# INTERFACE_rev2.net
KiCad netlist of a schematic drawn in Altium Designer
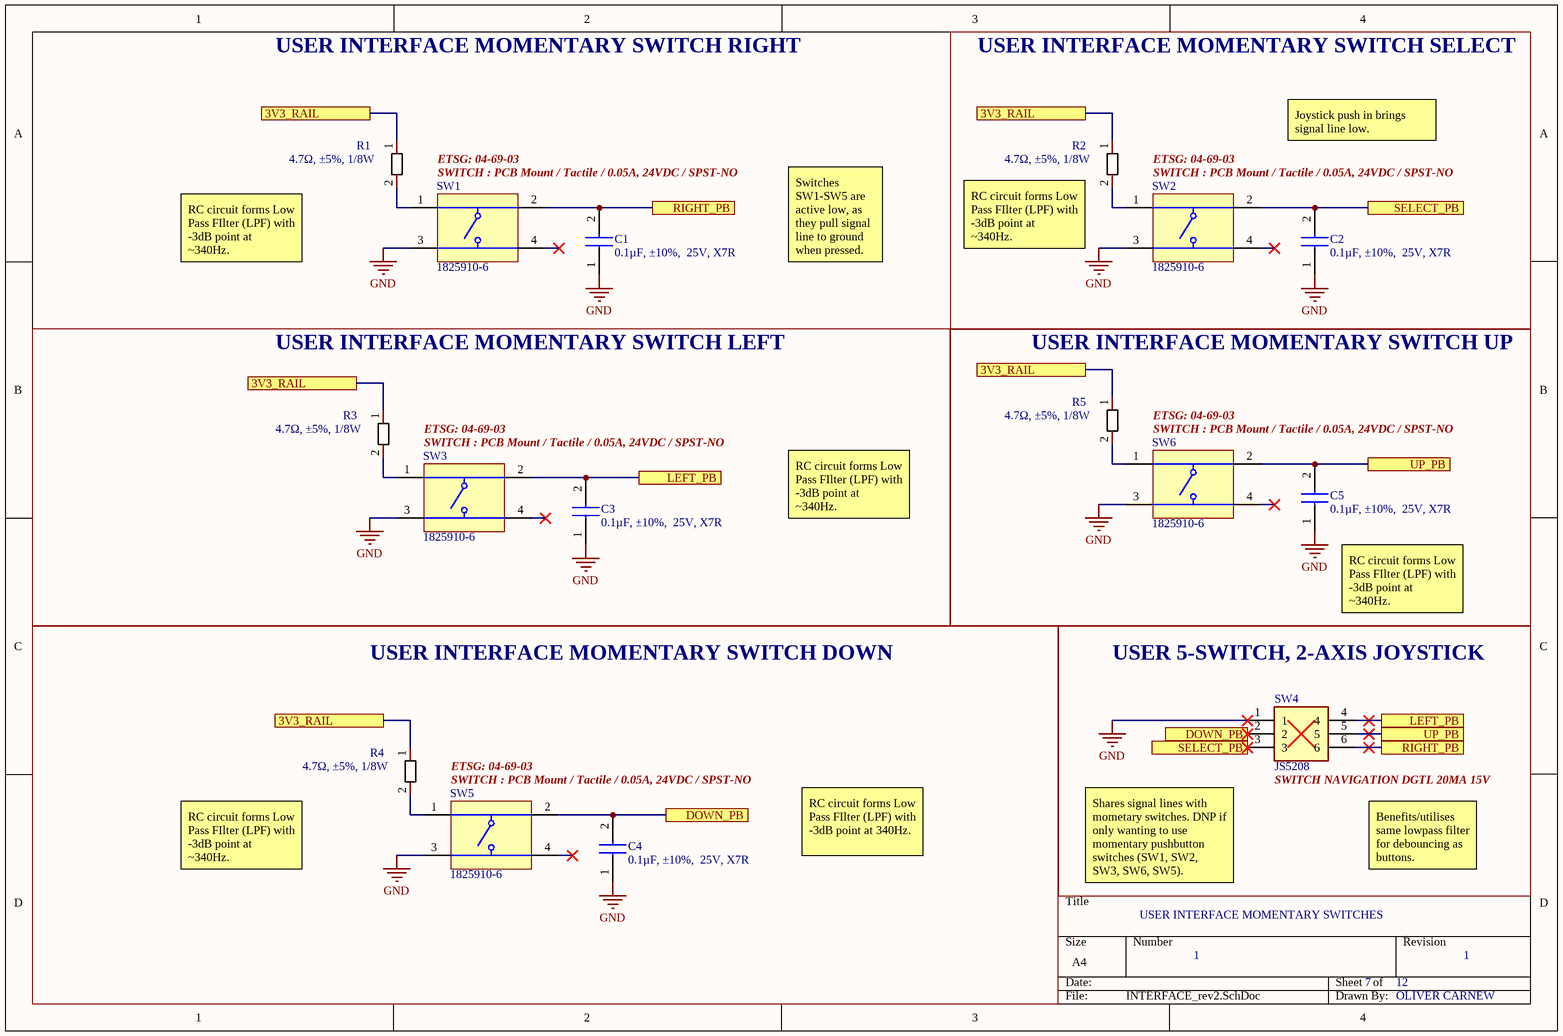
[diagram p0: INTERFACE_rev2.SchDoc]

(export (version "E")
  (design (tool "Eeschema 10.0.6"))
  (components
    (comp (ref "C1")
      (value "0.1µF, ±10%,  25V, X7R")
      (footprint "SamacSys:CAPC1005X55N")
      (description "Capacitor CAP CER 0.1UF 25V X7R 0402 CL05B104KA5NNNC")
      (fields
        (field (name "MANUFACTURER_PART_NUMBER") "CL05B104KA5NNNC")
        (field (name "MOUSER PART NUMBER") "187-CL05B104KA5NNNC")
      )
      (libsource (lib "*") (part "CL05B104KA5NNNC"))
    )
    (comp (ref "C2")
      (value "0.1µF, ±10%,  25V, X7R")
      (footprint "SamacSys:CAPC1005X55N")
      (description "Capacitor CAP CER 0.1UF 25V X7R 0402 CL05B104KA5NNNC")
      (fields
        (field (name "MANUFACTURER_PART_NUMBER") "CL05B104KA5NNNC")
        (field (name "MOUSER PART NUMBER") "187-CL05B104KA5NNNC")
      )
      (libsource (lib "*") (part "CL05B104KA5NNNC"))
    )
    (comp (ref "C3")
      (value "0.1µF, ±10%,  25V, X7R")
      (footprint "SamacSys:CAPC1005X55N")
      (description "Capacitor CAP CER 0.1UF 25V X7R 0402 CL05B104KA5NNNC")
      (fields
        (field (name "MANUFACTURER_PART_NUMBER") "CL05B104KA5NNNC")
        (field (name "MOUSER PART NUMBER") "187-CL05B104KA5NNNC")
      )
      (libsource (lib "*") (part "CL05B104KA5NNNC"))
    )
    (comp (ref "C4")
      (value "0.1µF, ±10%,  25V, X7R")
      (footprint "SamacSys:CAPC1005X55N")
      (description "Capacitor CAP CER 0.1UF 25V X7R 0402 CL05B104KA5NNNC")
      (fields
        (field (name "MANUFACTURER_PART_NUMBER") "CL05B104KA5NNNC")
        (field (name "MOUSER PART NUMBER") "187-CL05B104KA5NNNC")
      )
      (libsource (lib "*") (part "CL05B104KA5NNNC"))
    )
    (comp (ref "C5")
      (value "0.1µF, ±10%,  25V, X7R")
      (footprint "SamacSys:CAPC1005X55N")
      (description "Capacitor CAP CER 0.1UF 25V X7R 0402 CL05B104KA5NNNC")
      (fields
        (field (name "MANUFACTURER_PART_NUMBER") "CL05B104KA5NNNC")
        (field (name "MOUSER PART NUMBER") "187-CL05B104KA5NNNC")
      )
      (libsource (lib "*") (part "CL05B104KA5NNNC"))
    )
    (comp (ref "R1")
      (value "4.7Ω, ±5%, 1/8W")
      (footprint "SURFM RESISTOR")
      (libsource (lib "Control_unit") (part "0805-R"))
    )
    (comp (ref "R2")
      (value "4.7Ω, ±5%, 1/8W")
      (footprint "SURFM RESISTOR")
      (libsource (lib "Control_unit") (part "0805-R"))
    )
    (comp (ref "R3")
      (value "4.7Ω, ±5%, 1/8W")
      (footprint "SURFM RESISTOR")
      (libsource (lib "Control_unit") (part "0805-R"))
    )
    (comp (ref "R4")
      (value "4.7Ω, ±5%, 1/8W")
      (footprint "SURFM RESISTOR")
      (libsource (lib "Control_unit") (part "0805-R"))
    )
    (comp (ref "R5")
      (value "4.7Ω, ±5%, 1/8W")
      (footprint "SURFM RESISTOR")
      (libsource (lib "Control_unit") (part "0805-R"))
    )
    (comp (ref "SW1")
      (value "1825910-6")
      (footprint "TECO-1825910-6_V")
      (description "Tact Switch, SPST-NO, 0.05 A, -35 to 85 degC, 4-Pin THD, RoHS, Bulk")
      (fields (field (name "MANUFACTURER") "TE Connectivity"))
      (libsource (lib "Altium Content Vault") (part "SW-SPST-4_A"))
    )
    (comp (ref "SW2")
      (value "1825910-6")
      (footprint "TECO-1825910-6_V")
      (description "Tact Switch, SPST-NO, 0.05 A, -35 to 85 degC, 4-Pin THD, RoHS, Bulk")
      (fields (field (name "MANUFACTURER") "TE Connectivity"))
      (libsource (lib "Altium Content Vault") (part "SW-SPST-4_A"))
    )
    (comp (ref "SW3")
      (value "1825910-6")
      (footprint "TECO-1825910-6_V")
      (description "Tact Switch, SPST-NO, 0.05 A, -35 to 85 degC, 4-Pin THD, RoHS, Bulk")
      (fields (field (name "MANUFACTURER") "TE Connectivity"))
      (libsource (lib "Altium Content Vault") (part "SW-SPST-4_A"))
    )
    (comp (ref "SW4")
      (value "JS5208")
      (footprint "SamacSys:JS5208")
      (description "Switch")
      (fields (field (name "MOUSER PART NUMBER") "612-JS5208"))
      (libsource (lib "SamacSys") (part "JS5208"))
    )
    (comp (ref "SW5")
      (value "1825910-6")
      (footprint "TECO-1825910-6_V")
      (description "Tact Switch, SPST-NO, 0.05 A, -35 to 85 degC, 4-Pin THD, RoHS, Bulk")
      (fields (field (name "MANUFACTURER") "TE Connectivity"))
      (libsource (lib "Altium Content Vault") (part "SW-SPST-4_A"))
    )
    (comp (ref "SW6")
      (value "1825910-6")
      (footprint "TECO-1825910-6_V")
      (description "Tact Switch, SPST-NO, 0.05 A, -35 to 85 degC, 4-Pin THD, RoHS, Bulk")
      (fields (field (name "MANUFACTURER") "TE Connectivity"))
      (libsource (lib "Altium Content Vault") (part "SW-SPST-4_A"))
    )
  )
  (nets
    (net (code "1") (name "/3V3_RAIL") (class "Default")
      (node (ref "R1") (pin "1") (pinfunction "1_1") (pintype "passive"))
      (node (ref "R2") (pin "1") (pinfunction "1_1") (pintype "passive"))
      (node (ref "R3") (pin "1") (pinfunction "1_1") (pintype "passive"))
      (node (ref "R4") (pin "1") (pinfunction "1_1") (pintype "passive"))
      (node (ref "R5") (pin "1") (pinfunction "1_1") (pintype "passive"))
    )
    (net (code "2") (name "/DOWN_PB") (class "Default")
      (node (ref "C4") (pin "2") (pinfunction "2_2") (pintype "passive"))
      (node (ref "SW4") (pin "2") (pinfunction "2_2") (pintype "passive"))
      (node (ref "SW5") (pin "2") (pinfunction "2_2") (pintype "passive"))
    )
    (net (code "3") (name "/LEFT_PB") (class "Default")
      (node (ref "C3") (pin "2") (pinfunction "2_2") (pintype "passive"))
      (node (ref "SW3") (pin "2") (pinfunction "2_2") (pintype "passive"))
      (node (ref "SW4") (pin "4") (pinfunction "4_4") (pintype "passive"))
    )
    (net (code "4") (name "/RIGHT_PB") (class "Default")
      (node (ref "C1") (pin "2") (pinfunction "2_2") (pintype "passive"))
      (node (ref "SW1") (pin "2") (pinfunction "2_2") (pintype "passive"))
      (node (ref "SW4") (pin "6") (pinfunction "6_6") (pintype "passive"))
    )
    (net (code "5") (name "/SELECT_PB") (class "Default")
      (node (ref "C2") (pin "2") (pinfunction "2_2") (pintype "passive"))
      (node (ref "SW2") (pin "2") (pinfunction "2_2") (pintype "passive"))
      (node (ref "SW4") (pin "3") (pinfunction "3_3") (pintype "passive"))
    )
    (net (code "6") (name "/UP_PB") (class "Default")
      (node (ref "C5") (pin "2") (pinfunction "2_2") (pintype "passive"))
      (node (ref "SW4") (pin "5") (pinfunction "5_5") (pintype "passive"))
      (node (ref "SW6") (pin "2") (pinfunction "2_2") (pintype "passive"))
    )
    (net (code "7") (name "GND") (class "Default")
      (node (ref "C1") (pin "1") (pinfunction "1_1") (pintype "passive"))
      (node (ref "C2") (pin "1") (pinfunction "1_1") (pintype "passive"))
      (node (ref "C3") (pin "1") (pinfunction "1_1") (pintype "passive"))
      (node (ref "C4") (pin "1") (pinfunction "1_1") (pintype "passive"))
      (node (ref "C5") (pin "1") (pinfunction "1_1") (pintype "passive"))
      (node (ref "SW1") (pin "3") (pinfunction "3_3") (pintype "passive"))
      (node (ref "SW2") (pin "3") (pinfunction "3_3") (pintype "passive"))
      (node (ref "SW3") (pin "3") (pinfunction "3_3") (pintype "passive"))
      (node (ref "SW4") (pin "1") (pinfunction "1_1") (pintype "passive"))
      (node (ref "SW5") (pin "3") (pinfunction "3_3") (pintype "passive"))
      (node (ref "SW6") (pin "3") (pinfunction "3_3") (pintype "passive"))
    )
    (net (code "8") (name "Net-(R1-Pad2)") (class "Default")
      (node (ref "R1") (pin "2") (pinfunction "2_2") (pintype "passive"))
      (node (ref "SW1") (pin "1") (pinfunction "1_1") (pintype "passive"))
    )
    (net (code "9") (name "Net-(R2-Pad2)") (class "Default")
      (node (ref "R2") (pin "2") (pinfunction "2_2") (pintype "passive"))
      (node (ref "SW2") (pin "1") (pinfunction "1_1") (pintype "passive"))
    )
    (net (code "10") (name "Net-(R3-Pad2)") (class "Default")
      (node (ref "R3") (pin "2") (pinfunction "2_2") (pintype "passive"))
      (node (ref "SW3") (pin "1") (pinfunction "1_1") (pintype "passive"))
    )
    (net (code "11") (name "Net-(R4-Pad2)") (class "Default")
      (node (ref "R4") (pin "2") (pinfunction "2_2") (pintype "passive"))
      (node (ref "SW5") (pin "1") (pinfunction "1_1") (pintype "passive"))
    )
    (net (code "12") (name "Net-(R5-Pad2)") (class "Default")
      (node (ref "R5") (pin "2") (pinfunction "2_2") (pintype "passive"))
      (node (ref "SW6") (pin "1") (pinfunction "1_1") (pintype "passive"))
    )
    (net (code "13") (name "unconnected-(SW1-Pad4)") (class "Default")
      (node (ref "SW1") (pin "4") (pinfunction "4_4") (pintype "passive+no_connect"))
    )
    (net (code "14") (name "unconnected-(SW2-Pad4)") (class "Default")
      (node (ref "SW2") (pin "4") (pinfunction "4_4") (pintype "passive+no_connect"))
    )
    (net (code "15") (name "unconnected-(SW3-Pad4)") (class "Default")
      (node (ref "SW3") (pin "4") (pinfunction "4_4") (pintype "passive+no_connect"))
    )
    (net (code "16") (name "unconnected-(SW5-Pad4)") (class "Default")
      (node (ref "SW5") (pin "4") (pinfunction "4_4") (pintype "passive+no_connect"))
    )
    (net (code "17") (name "unconnected-(SW6-Pad4)") (class "Default")
      (node (ref "SW6") (pin "4") (pinfunction "4_4") (pintype "passive+no_connect"))
    )
  )
)
